# HV_boost.net
KiCad netlist of a schematic drawn in Altium Designer
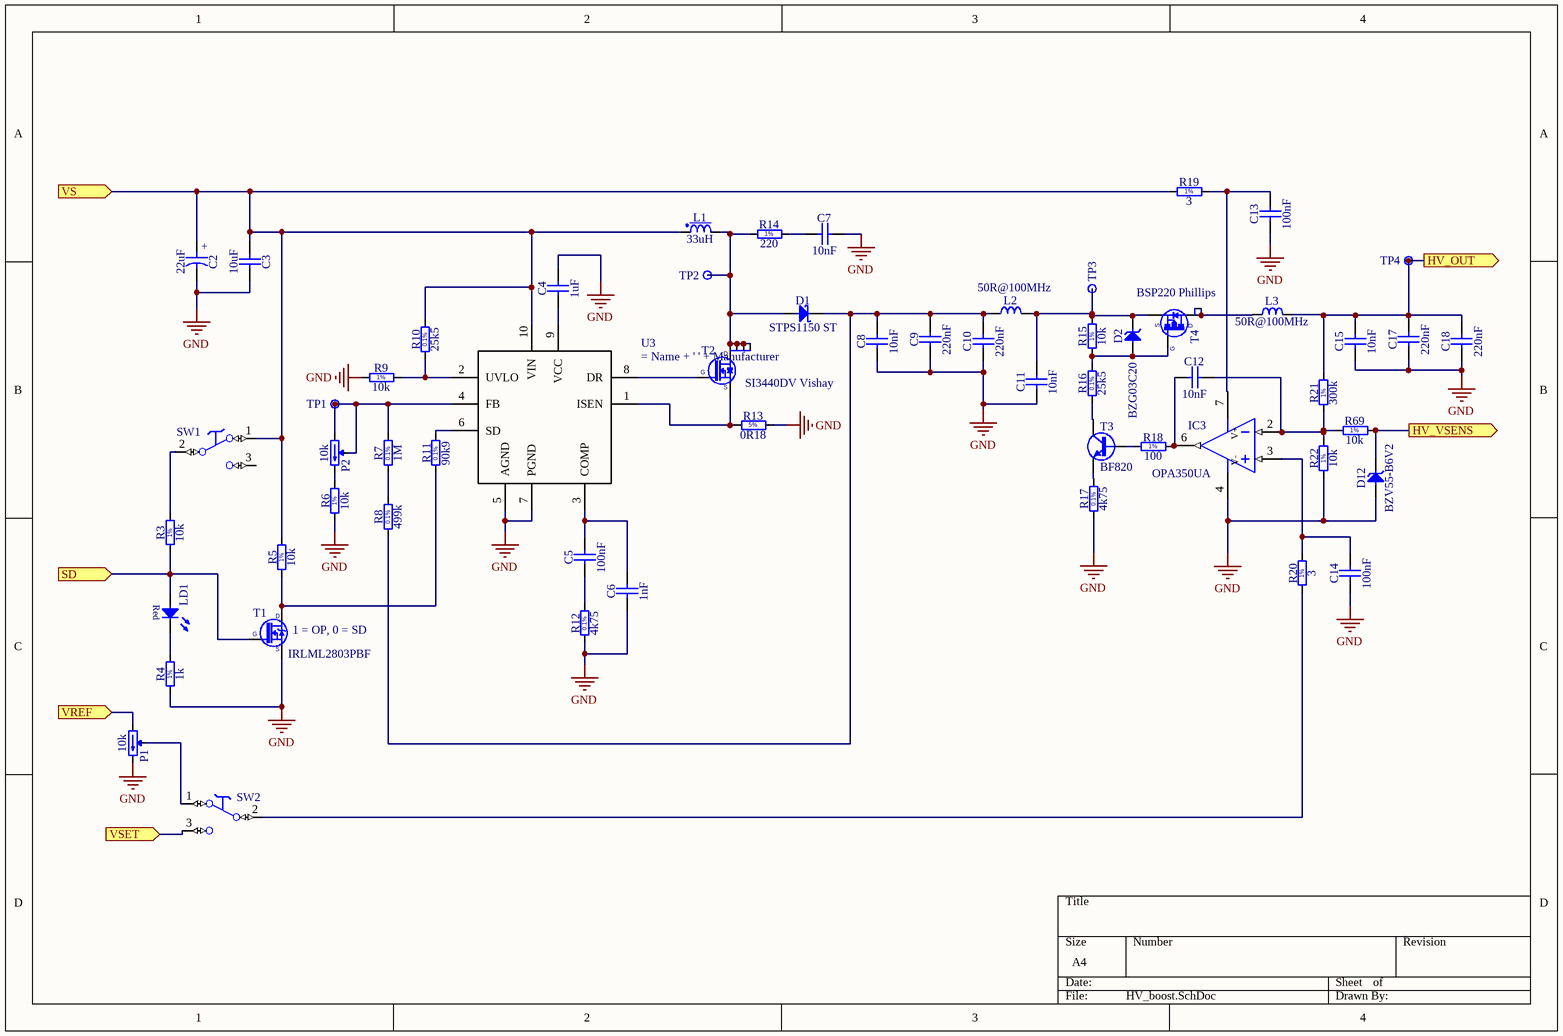
[diagram p0: HV_boost.SchDoc]

(export (version "E")
  (design (tool "Eeschema 10.0.6"))
  (components
    (comp (ref "C2")
      (value "22uF")
      (footprint "CAPAE530X540N")
      (description "Polarised capacitor")
      (fields
        (field (name "PART NUMBER") "CAE530-540_22UF_16V_20%")
        (field (name "VOLTAGE") "16V")
        (field (name "AUTHOR") "CERN DEM JLC")
      )
      (libsource (lib "Capacitors") (part "Capacitor - polarized"))
    )
    (comp (ref "C3")
      (value "10uF")
      (footprint "CAPC3216X180N")
      (description "Non-polarised capacitor")
      (fields
        (field (name "PART NUMBER") "CC1206_10UF_25V_10%_X7R")
        (field (name "VOLTAGE") "25V")
        (field (name "AUTHOR") "CERN DEM JLC")
      )
      (libsource (lib "Capacitors") (part "Capacitor - non polarized"))
    )
    (comp (ref "C4")
      (value "1uF")
      (footprint "CAPC2012X135N")
      (description "Non-polarised capacitor")
      (fields
        (field (name "PART NUMBER") "CC0805_1UF_16V_10%_X7R")
        (field (name "VOLTAGE") "16V")
        (field (name "AUTHOR") "CERN DEM JLC")
      )
      (libsource (lib "Capacitors") (part "Capacitor - non polarized"))
    )
    (comp (ref "C5")
      (value "100nF")
      (footprint "CAPC2012X135N")
      (description "Non-polarised capacitor")
      (fields
        (field (name "PART NUMBER") "CC0805_100NF_50V_10%_X7R")
        (field (name "VOLTAGE") "50V")
        (field (name "AUTHOR") "CERN DEM JLC")
      )
      (libsource (lib "Capacitors") (part "Capacitor - non polarized"))
    )
    (comp (ref "C6")
      (value "1nF")
      (footprint "CAPC2012X135N")
      (description "Non-polarised capacitor")
      (fields
        (field (name "PART NUMBER") "CC0805_1NF_50V_10%_X7R")
        (field (name "VOLTAGE") "50V")
        (field (name "AUTHOR") "CERN DEM JLC")
      )
      (libsource (lib "Capacitors") (part "Capacitor - non polarized"))
    )
    (comp (ref "C7")
      (value "10nF")
      (footprint "CAPC3216X100N")
      (description "Non-polarised capacitor")
      (fields
        (field (name "PART NUMBER") "CC1206_10NF_200V_5%_C0G")
        (field (name "VOLTAGE") "200V")
        (field (name "AUTHOR") "CERN DEM JLC")
      )
      (libsource (lib "Capacitors") (part "Capacitor - non polarized"))
    )
    (comp (ref "C8")
      (value "10nF")
      (footprint "CAPC3216X100N")
      (description "Non-polarised capacitor")
      (fields
        (field (name "PART NUMBER") "CC1206_10NF_200V_5%_C0G")
        (field (name "VOLTAGE") "200V")
        (field (name "AUTHOR") "CERN DEM JLC")
      )
      (libsource (lib "Capacitors") (part "Capacitor - non polarized"))
    )
    (comp (ref "C9")
      (value "220nF")
      (footprint "CAPR500-350X720X850")
      (description "Non-polarised capacitor")
      (fields
        (field (name "PART NUMBER") "CPER_220NF_100V_10%_500-350X720X850")
        (field (name "VOLTAGE") "100VDC/63VAC")
        (field (name "AUTHOR") "CERN DEM JLC")
      )
      (libsource (lib "Capacitors") (part "Capacitor - non polarized"))
    )
    (comp (ref "C10")
      (value "220nF")
      (footprint "CAPR500-350X720X850")
      (description "Non-polarised capacitor")
      (fields
        (field (name "PART NUMBER") "CPER_220NF_100V_10%_500-350X720X850")
        (field (name "VOLTAGE") "100VDC/63VAC")
        (field (name "AUTHOR") "CERN DEM JLC")
      )
      (libsource (lib "Capacitors") (part "Capacitor - non polarized"))
    )
    (comp (ref "C11")
      (value "10nF")
      (footprint "CAPC3216X100N")
      (description "Non-polarised capacitor")
      (fields
        (field (name "PART NUMBER") "CC1206_10NF_200V_5%_C0G")
        (field (name "VOLTAGE") "200V")
        (field (name "AUTHOR") "CERN DEM JLC")
      )
      (libsource (lib "Capacitors") (part "Capacitor - non polarized"))
    )
    (comp (ref "C12")
      (value "10nF")
      (footprint "CAPC2012X135N")
      (description "Non-polarised capacitor")
      (fields
        (field (name "PART NUMBER") "CC0805_10NF_50V_5%_X7R")
        (field (name "VOLTAGE") "50V")
        (field (name "AUTHOR") "CERN DEM JLC")
      )
      (libsource (lib "Capacitors") (part "Capacitor - non polarized"))
    )
    (comp (ref "C13")
      (value "100nF")
      (footprint "CAPC2012X135N")
      (description "Non-polarised capacitor")
      (fields
        (field (name "PART NUMBER") "CC0805_100NF_50V_10%_X7R")
        (field (name "VOLTAGE") "50V")
        (field (name "AUTHOR") "CERN DEM JLC")
      )
      (libsource (lib "Capacitors") (part "Capacitor - non polarized"))
    )
    (comp (ref "C14")
      (value "100nF")
      (footprint "CAPC2012X135N")
      (description "Non-polarised capacitor")
      (fields
        (field (name "PART NUMBER") "CC0805_100NF_50V_10%_X7R")
        (field (name "VOLTAGE") "50V")
        (field (name "AUTHOR") "CERN DEM JLC")
      )
      (libsource (lib "Capacitors") (part "Capacitor - non polarized"))
    )
    (comp (ref "C15")
      (value "10nF")
      (footprint "CAPC3216X100N")
      (description "Non-polarised capacitor")
      (fields
        (field (name "PART NUMBER") "CC1206_10NF_200V_5%_C0G")
        (field (name "VOLTAGE") "200V")
        (field (name "AUTHOR") "CERN DEM JLC")
      )
      (libsource (lib "Capacitors") (part "Capacitor - non polarized"))
    )
    (comp (ref "C17")
      (value "220nF")
      (footprint "CAPR500-350X720X850")
      (description "Non-polarised capacitor")
      (fields
        (field (name "PART NUMBER") "CPER_220NF_100V_10%_500-350X720X850")
        (field (name "VOLTAGE") "100VDC/63VAC")
        (field (name "AUTHOR") "CERN DEM JLC")
      )
      (libsource (lib "Capacitors") (part "Capacitor - non polarized"))
    )
    (comp (ref "C18")
      (value "220nF")
      (footprint "CAPR500-350X720X850")
      (description "Non-polarised capacitor")
      (fields
        (field (name "PART NUMBER") "CPER_220NF_100V_10%_500-350X720X850")
        (field (name "VOLTAGE") "100VDC/63VAC")
        (field (name "AUTHOR") "CERN DEM JLC")
      )
      (libsource (lib "Capacitors") (part "Capacitor - non polarized"))
    )
    (comp (ref "D1")
      (value "STPS1150 ST")
      (footprint "DIOM5027X244N")
      (description "Diode Schottky  Anode Pin 1 Cathode Pin 3 (Pas de pin 2)")
      (fields (field (name "MANUFACTURER") "ST"))
      (libsource (lib "Additional") (part "STPS1150"))
    )
    (comp (ref "D2")
      (value "BZG03C20")
      (footprint "DIOM5326X230N")
      (description "Zener Diode")
      (fields
        (field (name "VOLTAGE") "20V")
        (field (name "POWER") "1.25W")
        (field (name "AUTHOR") "CERN DEM JLC")
      )
      (libsource (lib "ICs And Semiconductors") (part "Diode Zener"))
    )
    (comp (ref "D12")
      (value "BZV55-B6V2")
      (footprint "DIOMELF3515N")
      (description "Zener Diode")
      (fields
        (field (name "VOLTAGE") "6V2")
        (field (name "POWER") "500mW")
        (field (name "AUTHOR") "CERN DEM JLC")
      )
      (libsource (lib "ICs And Semiconductors") (part "Diode Zener"))
    )
    (comp (ref "IC3")
      (value "OPA350UA")
      (footprint "SOIC127P600X175-8N")
      (description "Operational Amplifier")
      (fields (field (name "MANUFACTURER") "TEXAS INSTRUMENTS") (field (name "AUTHOR") "CERN DEM JLC"))
      (libsource (lib "ICs And Semiconductors") (part "Operational Amplifier Type1"))
    )
    (comp (ref "L1")
      (value "33uH")
      (footprint "IND_PANASONIC_ELL6RH")
      (description "Inductor With Magnetic core 1Dot")
      (fields
        (field (name "PART NUMBER") "IND_33UH_20%_PANASONIC_ELL6RH330M")
        (field (name "POWER") "600mA")
        (field (name "AUTHOR") "CERN DEM JMW")
      )
      (libsource (lib "Inductors & Transformers") (part "Inductor With Magnetic core 1Dot"))
    )
    (comp (ref "L2")
      (value "50R@100MHz")
      (footprint "IND_MURATA_BLM31PG")
      (description "Inductor")
      (fields
        (field (name "PART NUMBER") "IND1206_MURATA_BLM31PG500SN1")
        (field (name "POWER") "3.5A")
        (field (name "AUTHOR") "CERN DEM JLC")
      )
      (libsource (lib "Inductors & Transformers") (part "Inductor"))
    )
    (comp (ref "L3")
      (value "50R@100MHz")
      (footprint "IND_MURATA_BLM31PG")
      (description "Inductor")
      (fields
        (field (name "PART NUMBER") "IND1206_MURATA_BLM31PG500SN1")
        (field (name "POWER") "3.5A")
        (field (name "AUTHOR") "CERN DEM JLC")
      )
      (libsource (lib "Inductors & Transformers") (part "Inductor"))
    )
    (comp (ref "LD1")
      (value "Super Red")
      (footprint "LED_OSRAM_LSR976")
      (description "LED Red 1C 2A")
      (fields
        (field (name "PART NUMBER") "LED_OSRAM_LSR976")
        (field (name "MANUFACTURER") "OSRAM")
        (field (name "AUTHOR") "CERN DEM JLC")
      )
      (libsource (lib "ICs And Semiconductors") (part "LED Red 1C 2A"))
    )
    (comp (ref "P1")
      (value "10k")
      (footprint "TRIM_BOURNS_3266W")
      (description "Trimming Potentiometer")
      (fields
        (field (name "PART NUMBER") "TRIM_12T_10K_BOURNS_3266W-1-103LF")
        (field (name "POWER") "0.25W")
        (field (name "AUTHOR") "CERN DEM JLC")
      )
      (libsource (lib "Resistors") (part "Trimming Potentiometer"))
    )
    (comp (ref "P2")
      (value "10k")
      (footprint "TRIM_BOURNS_3266W")
      (description "Trimming Potentiometer")
      (fields
        (field (name "PART NUMBER") "TRIM_12T_10K_BOURNS_3266W-1-103LF")
        (field (name "POWER") "0.25W")
        (field (name "AUTHOR") "CERN DEM JLC")
      )
      (libsource (lib "Resistors") (part "Trimming Potentiometer"))
    )
    (comp (ref "R3")
      (value "10k")
      (footprint "RESC2012X60N")
      (description "Resistor - 1%")
      (fields
        (field (name "PART NUMBER") "R0805_10K_1%_0.125W_100PPM")
        (field (name "POWER") "0.125W")
        (field (name "AUTHOR") "CERN DEM JLC")
      )
      (libsource (lib "Resistors") (part "Resistor - 1%"))
    )
    (comp (ref "R4")
      (value "1k")
      (footprint "RESC2012X60N")
      (description "Resistor - 1%")
      (fields
        (field (name "PART NUMBER") "R0805_1K_1%_0.33W_100PPM_VISHAY_CRCW-HP")
        (field (name "POWER") "0.33W")
        (field (name "AUTHOR") "CERN DEM JLC")
      )
      (libsource (lib "Resistors") (part "Resistor - 1%"))
    )
    (comp (ref "R5")
      (value "10k")
      (footprint "RESC2012X60N")
      (description "Resistor - 1%")
      (fields
        (field (name "PART NUMBER") "R0805_10K_1%_0.125W_100PPM")
        (field (name "POWER") "0.125W")
        (field (name "AUTHOR") "CERN DEM JLC")
      )
      (libsource (lib "Resistors") (part "Resistor - 1%"))
    )
    (comp (ref "R6")
      (value "10k")
      (footprint "RESC2012X60N")
      (description "Resistor - 1%")
      (fields
        (field (name "PART NUMBER") "R0805_10K_1%_0.125W_100PPM")
        (field (name "POWER") "0.125W")
        (field (name "AUTHOR") "CERN DEM JLC")
      )
      (libsource (lib "Resistors") (part "Resistor - 1%"))
    )
    (comp (ref "R7")
      (value "1M")
      (footprint "RESC2012X60N")
      (description "Resistor - 0.1%")
      (fields
        (field (name "PART NUMBER") "R0805_1M_0.1%_0.1W_25PPM")
        (field (name "POWER") "0.1W")
        (field (name "AUTHOR") "CERN DEM JLC")
      )
      (libsource (lib "Resistors") (part "Resistor - 0.1%"))
    )
    (comp (ref "R8")
      (value "499k")
      (footprint "RESC2012X60N")
      (description "Resistor - 0.1%")
      (fields
        (field (name "PART NUMBER") "R0805_499K_0.1%_0.25W_25PPM_150V")
        (field (name "POWER") "0.25W")
        (field (name "AUTHOR") "CERN DEM BC")
      )
      (libsource (lib "Resistors") (part "Resistor - 0.1%"))
    )
    (comp (ref "R9")
      (value "10k")
      (footprint "RESC2012X60N")
      (description "Resistor - 1%")
      (fields
        (field (name "PART NUMBER") "R0805_10K_1%_0.125W_100PPM")
        (field (name "POWER") "0.125W")
        (field (name "AUTHOR") "CERN DEM JLC")
      )
      (libsource (lib "Resistors") (part "Resistor - 1%"))
    )
    (comp (ref "R10")
      (value "25k5")
      (footprint "RESC2012X60N")
      (description "Resistor - 0.1%")
      (fields
        (field (name "PART NUMBER") "R0805_25K5_0.1%_0.1W_10PPM")
        (field (name "POWER") "0.1W")
        (field (name "AUTHOR") "CERN DEM JLC")
      )
      (libsource (lib "Resistors") (part "Resistor - 0.1%"))
    )
    (comp (ref "R11")
      (value "90k9")
      (footprint "RESC2012X60N")
      (description "Resistor - 0.1%")
      (fields
        (field (name "PART NUMBER") "R0805_90K9_0.1%_0.1W_10PPM")
        (field (name "POWER") "0.1W")
        (field (name "AUTHOR") "CERN DEM JLC")
      )
      (libsource (lib "Resistors") (part "Resistor - 0.1%"))
    )
    (comp (ref "R12")
      (value "4k75")
      (footprint "RESC2012X60N")
      (description "Resistor - 0.1%")
      (fields
        (field (name "PART NUMBER") "R0805_4K75_0.1%_0.1W_10PPM")
        (field (name "POWER") "0.1W")
        (field (name "AUTHOR") "CERN DEM JLC")
      )
      (libsource (lib "Resistors") (part "Resistor - 0.1%"))
    )
    (comp (ref "R13")
      (value "0R18")
      (footprint "RESC2012X70N")
      (description "Resistor - 5%")
      (fields
        (field (name "PART NUMBER") "R0805_0R18_5%_0.25W_250PPM_PANASONIC_ERJ")
        (field (name "POWER") "0.25W")
        (field (name "AUTHOR") "CERN DEM JLC")
      )
      (libsource (lib "Resistors") (part "Resistor - 5%"))
    )
    (comp (ref "R14")
      (value "220")
      (footprint "RESC3216X65N")
      (description "Resistor - 1%")
      (fields
        (field (name "PART NUMBER") "R1206_220R_1%_0.25W_100PPM")
        (field (name "POWER") "0.25W")
        (field (name "AUTHOR") "CERN DEM JLC")
      )
      (libsource (lib "Resistors") (part "Resistor - 1%"))
    )
    (comp (ref "R15")
      (value "10k")
      (footprint "RESC2012X60N")
      (description "Resistor - 1%")
      (fields
        (field (name "PART NUMBER") "R0805_10K_1%_0.125W_100PPM")
        (field (name "POWER") "0.125W")
        (field (name "AUTHOR") "CERN DEM JLC")
      )
      (libsource (lib "Resistors") (part "Resistor - 1%"))
    )
    (comp (ref "R16")
      (value "25k5")
      (footprint "RESC2012X60N")
      (description "Resistor - 0.1%")
      (fields
        (field (name "PART NUMBER") "R0805_25K5_0.1%_0.1W_10PPM")
        (field (name "POWER") "0.1W")
        (field (name "AUTHOR") "CERN DEM JLC")
      )
      (libsource (lib "Resistors") (part "Resistor - 0.1%"))
    )
    (comp (ref "R17")
      (value "4k75")
      (footprint "RESC2012X60N")
      (description "Resistor - 0.1%")
      (fields
        (field (name "PART NUMBER") "R0805_4K75_0.1%_0.1W_10PPM")
        (field (name "POWER") "0.1W")
        (field (name "AUTHOR") "CERN DEM JLC")
      )
      (libsource (lib "Resistors") (part "Resistor - 0.1%"))
    )
    (comp (ref "R18")
      (value "100")
      (footprint "RESC2012X60N")
      (description "Resistor - 1%")
      (fields
        (field (name "PART NUMBER") "R0805_100R_1%_0.125W_100PPM")
        (field (name "POWER") "0.125W")
        (field (name "AUTHOR") "CERN DEM JLC")
      )
      (libsource (lib "Resistors") (part "Resistor - 1%"))
    )
    (comp (ref "R19")
      (value "3")
      (footprint "RESC2012X60N")
      (description "Resistor - 1%")
      (fields
        (field (name "PART NUMBER") "R0805_3R_1%_0.125W_200PPM")
        (field (name "POWER") "0.125W")
        (field (name "AUTHOR") "CERN DEM JLC")
      )
      (libsource (lib "Resistors") (part "Resistor - 1%"))
    )
    (comp (ref "R20")
      (value "3")
      (footprint "RESC2012X60N")
      (description "Resistor - 1%")
      (fields
        (field (name "PART NUMBER") "R0805_3R_1%_0.125W_200PPM")
        (field (name "POWER") "0.125W")
        (field (name "AUTHOR") "CERN DEM JLC")
      )
      (libsource (lib "Resistors") (part "Resistor - 1%"))
    )
    (comp (ref "R21")
      (value "300k")
      (footprint "RESC2012X60N")
      (description "Resistor - 1%")
      (fields
        (field (name "PART NUMBER") "R0805_300K_1%_0.125W_100PPM")
        (field (name "POWER") "0.125W")
        (field (name "AUTHOR") "CERN DEM JLC")
      )
      (libsource (lib "Resistors") (part "Resistor - 1%"))
    )
    (comp (ref "R22")
      (value "10k")
      (footprint "RESC2012X60N")
      (description "Resistor - 1%")
      (fields
        (field (name "PART NUMBER") "R0805_10K_1%_0.125W_100PPM")
        (field (name "POWER") "0.125W")
        (field (name "AUTHOR") "CERN DEM JLC")
      )
      (libsource (lib "Resistors") (part "Resistor - 1%"))
    )
    (comp (ref "R69")
      (value "10k")
      (footprint "RESC2012X60N")
      (description "Resistor - 1%")
      (fields
        (field (name "PART NUMBER") "R0805_10K_1%_0.125W_100PPM")
        (field (name "POWER") "0.125W")
        (field (name "AUTHOR") "CERN DEM JLC")
      )
      (libsource (lib "Resistors") (part "Resistor - 1%"))
    )
    (comp (ref "SW1")
      (value "Switch")
      (footprint "SW_TYCO_1-1437575-4")
      (description "SPDT Switch")
      (fields
        (field (name "PART NUMBER") "SW_TYCO_1-1437575-4")
        (field (name "MANUFACTURER") "TYCO")
        (field (name "AUTHOR") "CERN DEM JLC")
      )
      (libsource (lib "Eletro-mechanical") (part "SW SPDT 1NC-2C-3NO"))
    )
    (comp (ref "SW2")
      (value "Switch")
      (footprint "SW_TYCO_1-1437575-4")
      (description "SPDT Switch")
      (fields
        (field (name "PART NUMBER") "SW_TYCO_1-1437575-4")
        (field (name "MANUFACTURER") "TYCO")
        (field (name "AUTHOR") "CERN DEM JLC")
      )
      (libsource (lib "Eletro-mechanical") (part "SW SPDT 1NC-2C-3NO"))
    )
    (comp (ref "T1")
      (value "IRLML2803PBF")
      (footprint "SOT95P237X112-3N")
      (description "N-CHANNEL MOSFET WITH ZENER DIODE")
      (fields (field (name "MANUFACTURER") "INTERNATIONAL RECTIFIER") (field (name "AUTHOR") "CERN DEM JMW"))
      (libsource (lib "ICs And Semiconductors") (part "N-MOSFET-DZ 1G 2S 3D"))
    )
    (comp (ref "T2")
      (value "SI3440DV Vishay")
      (footprint "SOT95P280X110-6N")
      (description "N-Channel MOSFET")
      (fields (field (name "MANUFACTURER") "Vishay"))
      (libsource (lib "Additional") (part "SI3440DV"))
    )
    (comp (ref "T3")
      (value "BF820")
      (footprint "SOT95P230X110-3N")
      (description "NPN Transistor")
      (fields (field (name "MANUFACTURER") "NXP SEMICONDUCTORS") (field (name "AUTHOR") "CERN DEM JLC"))
      (libsource (lib "ICs And Semiconductors") (part "NPN B1 E2 C3"))
    )
    (comp (ref "T4")
      (value "BSP220 Phillips")
      (footprint "SOT230P700X175-4N")
      (description "P-Channel MOSFET")
      (fields (field (name "MANUFACTURER") "Phillips"))
      (libsource (lib "Additional") (part "BSP220"))
    )
    (comp (ref "TP1")
      (value "Test Point")
      (footprint "VERO_20-2136")
      (fields
        (field (name "PART NUMBER") "VERO_20-2136")
        (field (name "MANUFACTURER") "VERO TECHNOLOGIES")
        (field (name "MANUFACTURER PART NUMBER") "20-2136")
        (field (name "AUTHOR") "CERN DEM JLC")
      )
      (libsource (lib "Connectors") (part "Test Point"))
    )
    (comp (ref "TP2")
      (value "Test Point")
      (footprint "VERO_20-2136")
      (fields
        (field (name "PART NUMBER") "VERO_20-2136")
        (field (name "MANUFACTURER") "VERO TECHNOLOGIES")
        (field (name "MANUFACTURER PART NUMBER") "20-2136")
        (field (name "AUTHOR") "CERN DEM JLC")
      )
      (libsource (lib "Connectors") (part "Test Point"))
    )
    (comp (ref "TP3")
      (value "Test Point")
      (footprint "VERO_20-2136")
      (fields
        (field (name "PART NUMBER") "VERO_20-2136")
        (field (name "MANUFACTURER") "VERO TECHNOLOGIES")
        (field (name "MANUFACTURER PART NUMBER") "20-2136")
        (field (name "AUTHOR") "CERN DEM JLC")
      )
      (libsource (lib "Connectors") (part "Test Point"))
    )
    (comp (ref "TP4")
      (value "Test Point")
      (footprint "VERO_20-2136")
      (fields
        (field (name "PART NUMBER") "VERO_20-2136")
        (field (name "MANUFACTURER") "VERO TECHNOLOGIES")
        (field (name "MANUFACTURER PART NUMBER") "20-2136")
        (field (name "AUTHOR") "CERN DEM JLC")
      )
      (libsource (lib "Connectors") (part "Test Point"))
    )
    (comp (ref "U3")
      (value "LM3481")
      (footprint "SOP50P490X110-10N")
      (libsource (lib "Additional") (part "LM3481"))
    )
  )
  (nets
    (net (code "1") (name "/HV_OUT") (class "Default")
      (node (ref "C15") (pin "2") (pinfunction "2_2") (pintype "passive"))
      (node (ref "C17") (pin "2") (pinfunction "2_2") (pintype "passive"))
      (node (ref "C18") (pin "2") (pinfunction "2_2") (pintype "passive"))
      (node (ref "L3") (pin "2") (pinfunction "2_2") (pintype "passive"))
      (node (ref "R21") (pin "2") (pinfunction "2_2") (pintype "passive"))
      (node (ref "TP4") (pin "1") (pinfunction "1_1") (pintype "bidirectional"))
    )
    (net (code "2") (name "/HV_VSENS") (class "Default")
      (node (ref "D12") (pin "1") (pinfunction "C_1") (pintype "passive"))
      (node (ref "R69") (pin "2") (pinfunction "2_2") (pintype "passive"))
    )
    (net (code "3") (name "/SD") (class "Default")
      (node (ref "LD1") (pin "2") (pinfunction "A_2") (pintype "passive"))
      (node (ref "R3") (pin "1") (pinfunction "1_1") (pintype "passive"))
      (node (ref "T1") (pin "1") (pinfunction "G_1") (pintype "passive"))
    )
    (net (code "4") (name "/VREF") (class "Default")
      (node (ref "P1") (pin "1") (pinfunction "CCW_1") (pintype "passive"))
    )
    (net (code "5") (name "/VS") (class "Default")
      (node (ref "C2") (pin "1") (pinfunction "1_1") (pintype "passive"))
      (node (ref "C3") (pin "1") (pinfunction "1_1") (pintype "passive"))
      (node (ref "L1") (pin "1") (pinfunction "1_1") (pintype "passive"))
      (node (ref "R10") (pin "2") (pinfunction "2_2") (pintype "passive"))
      (node (ref "R19") (pin "1") (pinfunction "1_1") (pintype "passive"))
      (node (ref "R5") (pin "2") (pinfunction "2_2") (pintype "passive"))
      (node (ref "SW1") (pin "1") (pinfunction "NC_1") (pintype "bidirectional"))
      (node (ref "U3") (pin "10") (pinfunction "VIN_10") (pintype "passive"))
    )
    (net (code "6") (name "/VSET") (class "Default")
      (node (ref "SW2") (pin "3") (pinfunction "NO_3") (pintype "bidirectional"))
    )
    (net (code "7") (name "GND") (class "Default")
      (node (ref "C10") (pin "1") (pinfunction "1_1") (pintype "passive"))
      (node (ref "C11") (pin "1") (pinfunction "1_1") (pintype "passive"))
      (node (ref "C13") (pin "1") (pinfunction "1_1") (pintype "passive"))
      (node (ref "C14") (pin "1") (pinfunction "1_1") (pintype "passive"))
      (node (ref "C15") (pin "1") (pinfunction "1_1") (pintype "passive"))
      (node (ref "C17") (pin "1") (pinfunction "1_1") (pintype "passive"))
      (node (ref "C18") (pin "1") (pinfunction "1_1") (pintype "passive"))
      (node (ref "C2") (pin "2") (pinfunction "2_2") (pintype "passive"))
      (node (ref "C3") (pin "2") (pinfunction "2_2") (pintype "passive"))
      (node (ref "C4") (pin "2") (pinfunction "2_2") (pintype "passive"))
      (node (ref "C6") (pin "1") (pinfunction "1_1") (pintype "passive"))
      (node (ref "C7") (pin "2") (pinfunction "2_2") (pintype "passive"))
      (node (ref "C8") (pin "1") (pinfunction "1_1") (pintype "passive"))
      (node (ref "C9") (pin "1") (pinfunction "1_1") (pintype "passive"))
      (node (ref "D12") (pin "2") (pinfunction "A_2") (pintype "passive"))
      (node (ref "IC3") (pin "4") (pinfunction "V-_4") (pintype "power_in"))
      (node (ref "P1") (pin "3") (pinfunction "CW_3") (pintype "passive"))
      (node (ref "R12") (pin "1") (pinfunction "1_1") (pintype "passive"))
      (node (ref "R13") (pin "2") (pinfunction "2_2") (pintype "passive"))
      (node (ref "R17") (pin "1") (pinfunction "1_1") (pintype "passive"))
      (node (ref "R22") (pin "1") (pinfunction "1_1") (pintype "passive"))
      (node (ref "R4") (pin "1") (pinfunction "1_1") (pintype "passive"))
      (node (ref "R6") (pin "1") (pinfunction "1_1") (pintype "passive"))
      (node (ref "R9") (pin "1") (pinfunction "1_1") (pintype "passive"))
      (node (ref "T1") (pin "2") (pinfunction "S_2") (pintype "passive"))
      (node (ref "U3") (pin "5") (pinfunction "AGND_5") (pintype "passive"))
      (node (ref "U3") (pin "7") (pinfunction "PGND_7") (pintype "passive"))
    )
    (net (code "8") (name "Net-(C5-Pad1)") (class "Default")
      (node (ref "C5") (pin "1") (pinfunction "1_1") (pintype "passive"))
      (node (ref "R12") (pin "2") (pinfunction "2_2") (pintype "passive"))
    )
    (net (code "9") (name "Net-(C7-Pad1)") (class "Default")
      (node (ref "C7") (pin "1") (pinfunction "1_1") (pintype "passive"))
      (node (ref "R14") (pin "2") (pinfunction "2_2") (pintype "passive"))
    )
    (net (code "10") (name "Net-(D1-A)") (class "Default")
      (node (ref "D1") (pin "2") (pinfunction "A_2") (pintype "passive"))
      (node (ref "L1") (pin "2") (pinfunction "2_2") (pintype "passive"))
      (node (ref "R14") (pin "1") (pinfunction "1_1") (pintype "passive"))
      (node (ref "T2") (pin "1") (pinfunction "D_1") (pintype "passive"))
      (node (ref "T2") (pin "2") (pinfunction "D_2") (pintype "passive"))
      (node (ref "T2") (pin "5") (pinfunction "D_5") (pintype "passive"))
      (node (ref "T2") (pin "6") (pinfunction "D_6") (pintype "passive"))
      (node (ref "TP2") (pin "1") (pinfunction "1_1") (pintype "bidirectional"))
    )
    (net (code "11") (name "Net-(D1-C)") (class "Default")
      (node (ref "C10") (pin "2") (pinfunction "2_2") (pintype "passive"))
      (node (ref "C8") (pin "2") (pinfunction "2_2") (pintype "passive"))
      (node (ref "C9") (pin "2") (pinfunction "2_2") (pintype "passive"))
      (node (ref "D1") (pin "1") (pinfunction "C_1") (pintype "passive"))
      (node (ref "L2") (pin "1") (pinfunction "1_1") (pintype "passive"))
      (node (ref "R8") (pin "1") (pinfunction "1_1") (pintype "passive"))
    )
    (net (code "12") (name "Net-(D2-A)") (class "Default")
      (node (ref "D2") (pin "2") (pinfunction "A_2") (pintype "passive"))
      (node (ref "R15") (pin "1") (pinfunction "1_1") (pintype "passive"))
      (node (ref "R16") (pin "2") (pinfunction "2_2") (pintype "passive"))
      (node (ref "T4") (pin "1") (pinfunction "G_1") (pintype "passive"))
    )
    (net (code "13") (name "Net-(D2-C)") (class "Default")
      (node (ref "C11") (pin "2") (pinfunction "2_2") (pintype "passive"))
      (node (ref "D2") (pin "1") (pinfunction "C_1") (pintype "passive"))
      (node (ref "L2") (pin "2") (pinfunction "2_2") (pintype "passive"))
      (node (ref "R15") (pin "2") (pinfunction "2_2") (pintype "passive"))
      (node (ref "T4") (pin "3") (pinfunction "S_3") (pintype "passive"))
      (node (ref "TP3") (pin "1") (pinfunction "1_1") (pintype "bidirectional"))
    )
    (net (code "14") (name "Net-(IC3-IN+)") (class "Default")
      (node (ref "C14") (pin "2") (pinfunction "2_2") (pintype "passive"))
      (node (ref "IC3") (pin "3") (pinfunction "IN+_3") (pintype "input"))
      (node (ref "R20") (pin "2") (pinfunction "2_2") (pintype "passive"))
    )
    (net (code "15") (name "Net-(IC3-IN-)") (class "Default")
      (node (ref "C12") (pin "2") (pinfunction "2_2") (pintype "passive"))
      (node (ref "IC3") (pin "2") (pinfunction "IN-_2") (pintype "input"))
      (node (ref "R21") (pin "1") (pinfunction "1_1") (pintype "passive"))
      (node (ref "R22") (pin "2") (pinfunction "2_2") (pintype "passive"))
      (node (ref "R69") (pin "1") (pinfunction "1_1") (pintype "passive"))
    )
    (net (code "16") (name "Net-(IC3-OUT)") (class "Default")
      (node (ref "C12") (pin "1") (pinfunction "1_1") (pintype "passive"))
      (node (ref "IC3") (pin "6") (pinfunction "OUT_6") (pintype "output"))
      (node (ref "R18") (pin "2") (pinfunction "2_2") (pintype "passive"))
    )
    (net (code "17") (name "Net-(IC3-V+)") (class "Default")
      (node (ref "C13") (pin "2") (pinfunction "2_2") (pintype "passive"))
      (node (ref "IC3") (pin "7") (pinfunction "V+_7") (pintype "power_in"))
      (node (ref "R19") (pin "2") (pinfunction "2_2") (pintype "passive"))
    )
    (net (code "18") (name "Net-(L3-Pad1)") (class "Default")
      (node (ref "L3") (pin "1") (pinfunction "1_1") (pintype "passive"))
      (node (ref "T4") (pin "2") (pinfunction "D_2") (pintype "passive"))
      (node (ref "T4") (pin "4") (pinfunction "D_4") (pintype "passive"))
    )
    (net (code "19") (name "Net-(LD1-C)") (class "Default")
      (node (ref "LD1") (pin "1") (pinfunction "C_1") (pintype "passive"))
      (node (ref "R4") (pin "2") (pinfunction "2_2") (pintype "passive"))
    )
    (net (code "20") (name "Net-(P1-W)") (class "Default")
      (node (ref "P1") (pin "2") (pinfunction "W_2") (pintype "passive"))
      (node (ref "SW2") (pin "1") (pinfunction "NC_1") (pintype "bidirectional"))
    )
    (net (code "21") (name "Net-(P2-CCW)") (class "Default")
      (node (ref "P2") (pin "1") (pinfunction "CCW_1") (pintype "passive"))
      (node (ref "P2") (pin "2") (pinfunction "W_2") (pintype "passive"))
      (node (ref "R7") (pin "2") (pinfunction "2_2") (pintype "passive"))
      (node (ref "TP1") (pin "1") (pinfunction "1_1") (pintype "bidirectional"))
      (node (ref "U3") (pin "4") (pinfunction "FB_4") (pintype "passive"))
    )
    (net (code "22") (name "Net-(P2-CW)") (class "Default")
      (node (ref "P2") (pin "3") (pinfunction "CW_3") (pintype "passive"))
      (node (ref "R6") (pin "2") (pinfunction "2_2") (pintype "passive"))
    )
    (net (code "23") (name "Net-(R7-Pad1)") (class "Default")
      (node (ref "R7") (pin "1") (pinfunction "1_1") (pintype "passive"))
      (node (ref "R8") (pin "2") (pinfunction "2_2") (pintype "passive"))
    )
    (net (code "24") (name "Net-(SW1-C)") (class "Default")
      (node (ref "R3") (pin "2") (pinfunction "2_2") (pintype "passive"))
      (node (ref "SW1") (pin "2") (pinfunction "C_2") (pintype "bidirectional"))
    )
    (net (code "25") (name "Net-(SW2-C)") (class "Default")
      (node (ref "R20") (pin "1") (pinfunction "1_1") (pintype "passive"))
      (node (ref "SW2") (pin "2") (pinfunction "C_2") (pintype "bidirectional"))
    )
    (net (code "26") (name "Net-(T1-D)") (class "Default")
      (node (ref "R11") (pin "1") (pinfunction "1_1") (pintype "passive"))
      (node (ref "R5") (pin "1") (pinfunction "1_1") (pintype "passive"))
      (node (ref "T1") (pin "3") (pinfunction "D_3") (pintype "passive"))
    )
    (net (code "27") (name "Net-(T2-G)") (class "Default")
      (node (ref "T2") (pin "3") (pinfunction "G_3") (pintype "passive"))
      (node (ref "U3") (pin "8") (pinfunction "DR_8") (pintype "passive"))
    )
    (net (code "28") (name "Net-(T2-S)") (class "Default")
      (node (ref "R13") (pin "1") (pinfunction "1_1") (pintype "passive"))
      (node (ref "T2") (pin "4") (pinfunction "S_4") (pintype "passive"))
      (node (ref "U3") (pin "1") (pinfunction "ISEN_1") (pintype "passive"))
    )
    (net (code "29") (name "Net-(T3-B)") (class "Default")
      (node (ref "R18") (pin "1") (pinfunction "1_1") (pintype "passive"))
      (node (ref "T3") (pin "1") (pinfunction "B_1") (pintype "passive"))
    )
    (net (code "30") (name "Net-(T3-C)") (class "Default")
      (node (ref "R16") (pin "1") (pinfunction "1_1") (pintype "passive"))
      (node (ref "T3") (pin "3") (pinfunction "C_3") (pintype "passive"))
    )
    (net (code "31") (name "Net-(T3-E)") (class "Default")
      (node (ref "R17") (pin "2") (pinfunction "2_2") (pintype "passive"))
      (node (ref "T3") (pin "2") (pinfunction "E_2") (pintype "passive"))
    )
    (net (code "32") (name "Net-(U3-COMP)") (class "Default")
      (node (ref "C5") (pin "2") (pinfunction "2_2") (pintype "passive"))
      (node (ref "C6") (pin "2") (pinfunction "2_2") (pintype "passive"))
      (node (ref "U3") (pin "3") (pinfunction "COMP_3") (pintype "passive"))
    )
    (net (code "33") (name "Net-(U3-SD)") (class "Default")
      (node (ref "R11") (pin "2") (pinfunction "2_2") (pintype "passive"))
      (node (ref "U3") (pin "6") (pinfunction "SD_6") (pintype "passive"))
    )
    (net (code "34") (name "Net-(U3-UVLO)") (class "Default")
      (node (ref "R10") (pin "1") (pinfunction "1_1") (pintype "passive"))
      (node (ref "R9") (pin "2") (pinfunction "2_2") (pintype "passive"))
      (node (ref "U3") (pin "2") (pinfunction "UVLO_2") (pintype "passive"))
    )
    (net (code "35") (name "Net-(U3-VCC)") (class "Default")
      (node (ref "C4") (pin "1") (pinfunction "1_1") (pintype "passive"))
      (node (ref "U3") (pin "9") (pinfunction "VCC_9") (pintype "passive"))
    )
    (net (code "36") (name "unconnected-(SW1-NO-Pad3)") (class "Default")
      (node (ref "SW1") (pin "3") (pinfunction "NO_3") (pintype "bidirectional"))
    )
  )
)
